# 4ButtonSwitch_Rev2.net
KiCad netlist of a schematic drawn in EAGLE
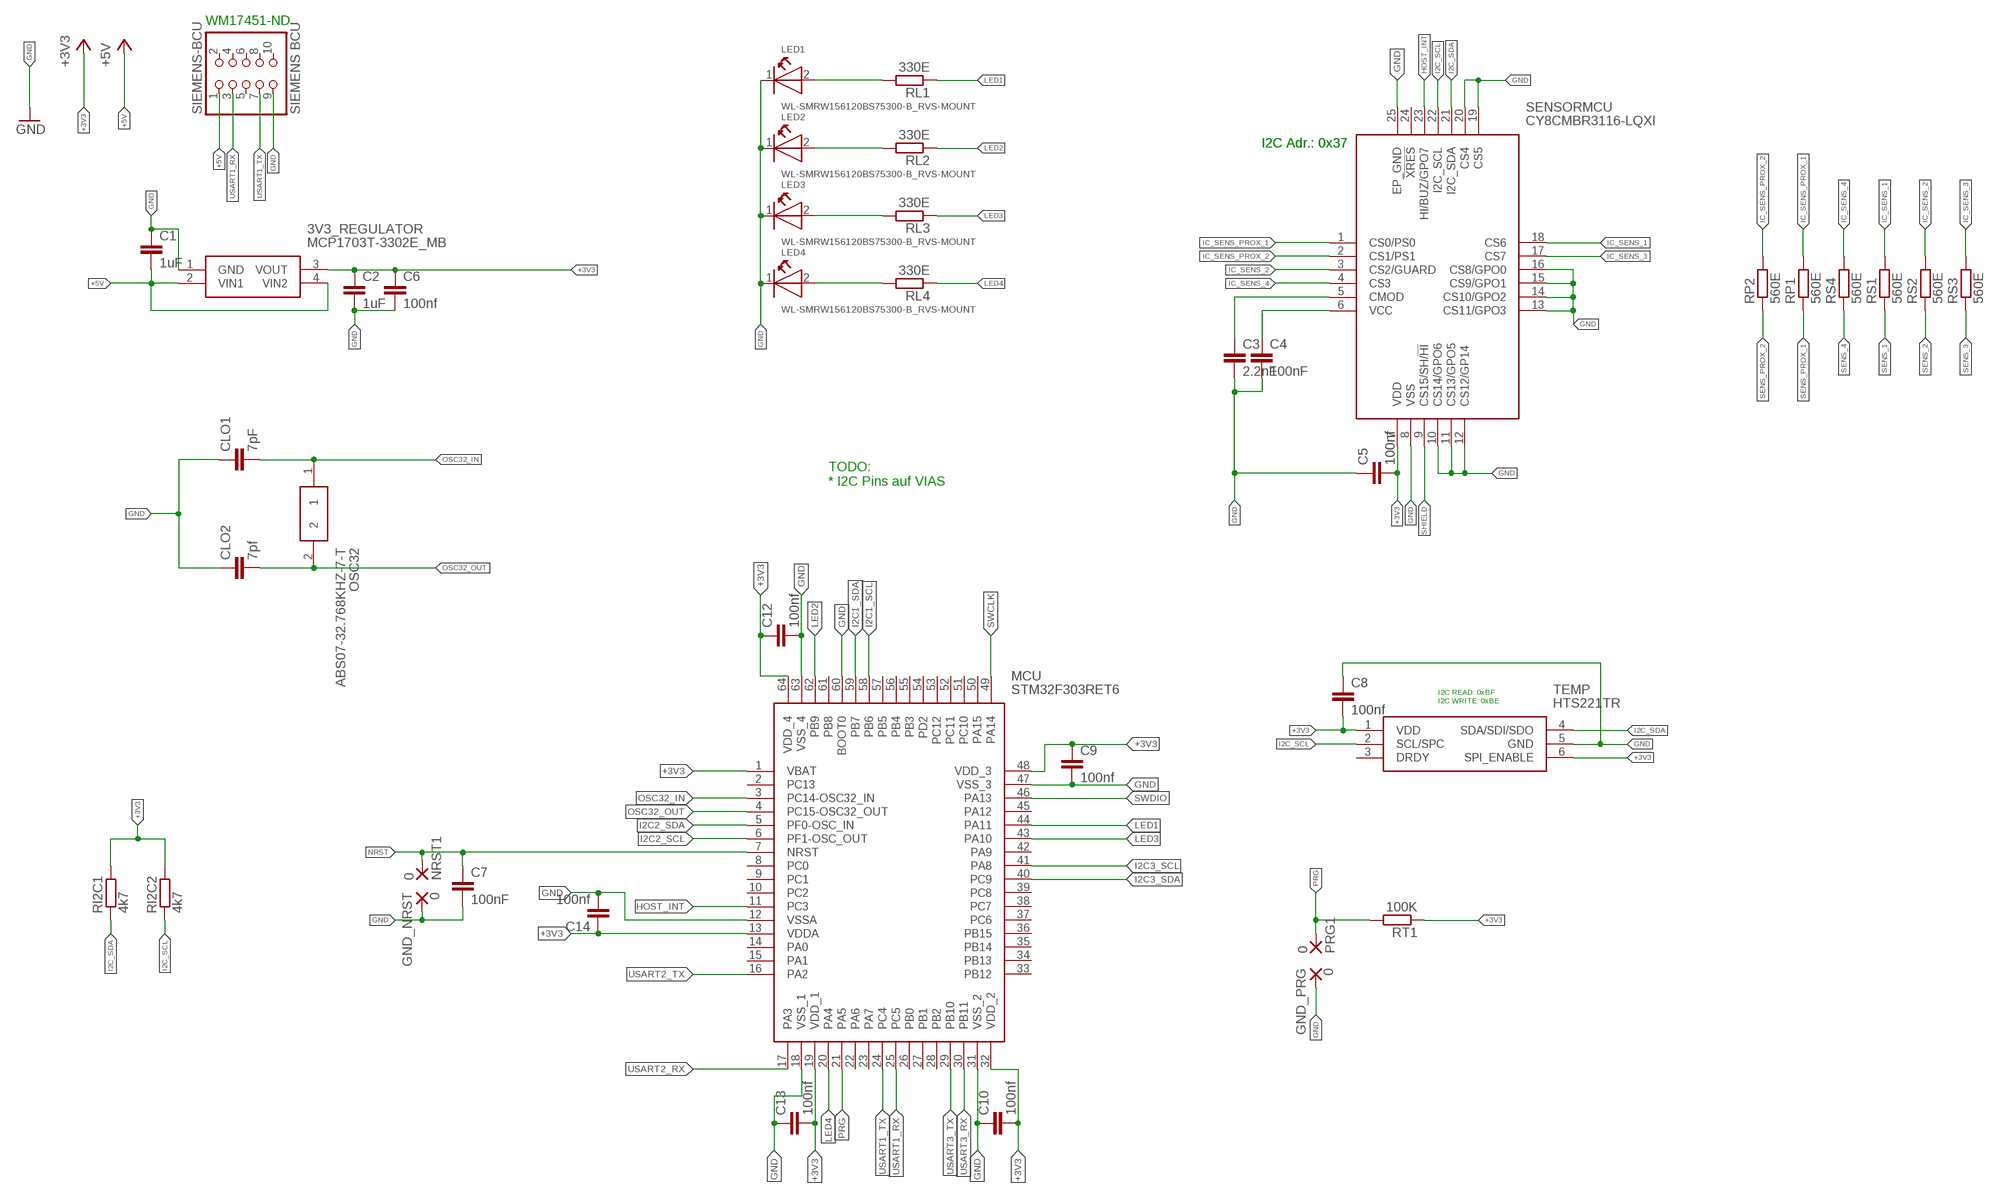
[diagram p0: schematic, sheet 1]

(export (version "E")
  (design (tool "Eeschema 10.0.6"))
  (components
    (comp (ref "3V3_REGULATOR")
      (value "MCP1703T-3302E_MB")
      (footprint "eagle-import:SOT-89(MB)")
      (fields
        (field (name "ARROW_PART_NUMBER") "MCP1703T-3302E/MB")
        (field (name "RS_PART_NUMBER") "9122916")
      )
      (libsource (lib "eagle-import") (part "MCP1703T-3302E_MB"))
    )
    (comp (ref "C1")
      (value "1uF")
      (footprint "eagle-import:C0402")
      (libsource (lib "eagle-import") (part "C-EUC0402"))
    )
    (comp (ref "C2")
      (value "1uF")
      (footprint "eagle-import:C0402")
      (libsource (lib "eagle-import") (part "C-EUC0402"))
    )
    (comp (ref "C3")
      (value "2.2nF")
      (footprint "eagle-import:C0402")
      (libsource (lib "eagle-import") (part "C-EUC0402"))
    )
    (comp (ref "C4")
      (value "100nF")
      (footprint "eagle-import:C0402")
      (libsource (lib "eagle-import") (part "C-EUC0402"))
    )
    (comp (ref "C5")
      (value "100nf")
      (footprint "eagle-import:C0402")
      (libsource (lib "eagle-import") (part "C-EUC0402"))
    )
    (comp (ref "C6")
      (value "100nf")
      (footprint "eagle-import:C0402")
      (libsource (lib "eagle-import") (part "C-EUC0402"))
    )
    (comp (ref "C7")
      (value "100nF")
      (footprint "eagle-import:C0402")
      (libsource (lib "eagle-import") (part "C-EUC0402"))
    )
    (comp (ref "C8")
      (value "100nf")
      (footprint "eagle-import:C0402")
      (libsource (lib "eagle-import") (part "C-EUC0402"))
    )
    (comp (ref "C9")
      (value "100nf")
      (footprint "eagle-import:C0402")
      (libsource (lib "eagle-import") (part "C-EUC0402"))
    )
    (comp (ref "C10")
      (value "100nf")
      (footprint "eagle-import:C0402")
      (libsource (lib "eagle-import") (part "C-EUC0402"))
    )
    (comp (ref "C12")
      (value "100nf")
      (footprint "eagle-import:C0402")
      (libsource (lib "eagle-import") (part "C-EUC0402"))
    )
    (comp (ref "C13")
      (value "100nf")
      (footprint "eagle-import:C0402")
      (libsource (lib "eagle-import") (part "C-EUC0402"))
    )
    (comp (ref "C14")
      (value "100nf")
      (footprint "eagle-import:C0402")
      (libsource (lib "eagle-import") (part "C-EUC0402"))
    )
    (comp (ref "CLO1")
      (value "7pF")
      (footprint "eagle-import:C0402")
      (libsource (lib "eagle-import") (part "C-EUC0402"))
    )
    (comp (ref "CLO2")
      (value "7pf")
      (footprint "eagle-import:C0402")
      (libsource (lib "eagle-import") (part "C-EUC0402"))
    )
    (comp (ref "GND_NRST")
      (value "0")
      (footprint "eagle-import:SMD2,54-5,08")
      (libsource (lib "eagle-import") (part "SMD5"))
    )
    (comp (ref "GND_PRG")
      (value "0")
      (footprint "eagle-import:SMD2,54-5,08")
      (libsource (lib "eagle-import") (part "SMD5"))
    )
    (comp (ref "LED1")
      (value "WL-SMRW156120BS75300-B_RVS-MOUNT")
      (footprint "eagle-import:WL-SMRW-1206-CYLDR-REVERSE-MOUNT")
      (libsource (lib "eagle-import") (part "WL-SMRW156120BS75300-B_RVS-MOUNT"))
    )
    (comp (ref "LED2")
      (value "WL-SMRW156120BS75300-B_RVS-MOUNT")
      (footprint "eagle-import:WL-SMRW-1206-CYLDR-REVERSE-MOUNT")
      (libsource (lib "eagle-import") (part "WL-SMRW156120BS75300-B_RVS-MOUNT"))
    )
    (comp (ref "LED3")
      (value "WL-SMRW156120BS75300-B_RVS-MOUNT")
      (footprint "eagle-import:WL-SMRW-1206-CYLDR-REVERSE-MOUNT")
      (libsource (lib "eagle-import") (part "WL-SMRW156120BS75300-B_RVS-MOUNT"))
    )
    (comp (ref "LED4")
      (value "WL-SMRW156120BS75300-B_RVS-MOUNT")
      (footprint "eagle-import:WL-SMRW-1206-CYLDR-REVERSE-MOUNT")
      (libsource (lib "eagle-import") (part "WL-SMRW156120BS75300-B_RVS-MOUNT"))
    )
    (comp (ref "MCU")
      (value "STM32F303RET6")
      (footprint "eagle-import:QFP50P1200X1200X160-64N")
      (fields (field (name "RS_PART_NUMBER") "1458887"))
      (libsource (lib "eagle-import") (part "STM32F303RET6"))
    )
    (comp (ref "NRST1")
      (value "0")
      (footprint "eagle-import:SMD2,54-5,08")
      (libsource (lib "eagle-import") (part "SMD5"))
    )
    (comp (ref "OSC32")
      (value "ABS07-32.768KHZ-7-T")
      (footprint "eagle-import:ABS-07")
      (fields (field (name "RS_PART_NUMBER") "1712773P"))
      (libsource (lib "eagle-import") (part "ABS07-32.768KHZ-7-T"))
    )
    (comp (ref "PRG1")
      (value "0")
      (footprint "eagle-import:SMD2,54-5,08")
      (libsource (lib "eagle-import") (part "SMD5"))
    )
    (comp (ref "RI2C1")
      (value "4k7")
      (footprint "eagle-import:R0402")
      (libsource (lib "eagle-import") (part "R-EU_R0402"))
    )
    (comp (ref "RI2C2")
      (value "4k7")
      (footprint "eagle-import:R0402")
      (libsource (lib "eagle-import") (part "R-EU_R0402"))
    )
    (comp (ref "RL1")
      (value "330E")
      (footprint "eagle-import:R0402")
      (libsource (lib "eagle-import") (part "R-EU_R0402"))
    )
    (comp (ref "RL2")
      (value "330E")
      (footprint "eagle-import:R0402")
      (libsource (lib "eagle-import") (part "R-EU_R0402"))
    )
    (comp (ref "RL3")
      (value "330E")
      (footprint "eagle-import:R0402")
      (libsource (lib "eagle-import") (part "R-EU_R0402"))
    )
    (comp (ref "RL4")
      (value "330E")
      (footprint "eagle-import:R0402")
      (libsource (lib "eagle-import") (part "R-EU_R0402"))
    )
    (comp (ref "RP1")
      (value "560E")
      (footprint "eagle-import:R0402")
      (libsource (lib "eagle-import") (part "R-EU_R0402"))
    )
    (comp (ref "RP2")
      (value "560E")
      (footprint "eagle-import:R0402")
      (libsource (lib "eagle-import") (part "R-EU_R0402"))
    )
    (comp (ref "RS1")
      (value "560E")
      (footprint "eagle-import:R0402")
      (libsource (lib "eagle-import") (part "R-EU_R0402"))
    )
    (comp (ref "RS2")
      (value "560E")
      (footprint "eagle-import:R0402")
      (libsource (lib "eagle-import") (part "R-EU_R0402"))
    )
    (comp (ref "RS3")
      (value "560E")
      (footprint "eagle-import:R0402")
      (libsource (lib "eagle-import") (part "R-EU_R0402"))
    )
    (comp (ref "RS4")
      (value "560E")
      (footprint "eagle-import:R0402")
      (libsource (lib "eagle-import") (part "R-EU_R0402"))
    )
    (comp (ref "RT1")
      (value "100K")
      (footprint "eagle-import:R0402")
      (libsource (lib "eagle-import") (part "R-EU_R0402"))
    )
    (comp (ref "SENSORMCU")
      (value "CY8CMBR3116-LQXI")
      (footprint "eagle-import:QFN50P400X400X60-25N")
      (fields (field (name "RS_PART_NUMBER") "1242976P"))
      (libsource (lib "eagle-import") (part "CY8CMBR3116-LQXI"))
    )
    (comp (ref "SIEMENS-BCU")
      (value "SIEMENS BCU")
      (footprint "eagle-import:2X05SMD")
      (libsource (lib "eagle-import") (part "PINHD-2X5_2.54-SMD"))
    )
    (comp (ref "TEMP")
      (value "HTS221TR")
      (footprint "eagle-import:HLGA-6L")
      (fields (field (name "RS_PART_NUMBER") "1660935"))
      (libsource (lib "eagle-import") (part "HTS221TR"))
    )
  )
  (nets
    (net (code "1") (name "+3V3") (class "Default")
      (node (ref "3V3_REGULATOR") (pin "3") (pinfunction "VOUT_3") (pintype "bidirectional"))
      (node (ref "C10") (pin "2") (pinfunction "2_2") (pintype "passive"))
      (node (ref "C12") (pin "1") (pinfunction "1_1") (pintype "passive"))
      (node (ref "C13") (pin "2") (pinfunction "2_2") (pintype "passive"))
      (node (ref "C14") (pin "1") (pinfunction "1_1") (pintype "passive"))
      (node (ref "C2") (pin "1") (pinfunction "1_1") (pintype "passive"))
      (node (ref "C5") (pin "2") (pinfunction "2_2") (pintype "passive"))
      (node (ref "C6") (pin "1") (pinfunction "1_1") (pintype "passive"))
      (node (ref "C8") (pin "2") (pinfunction "2_2") (pintype "passive"))
      (node (ref "C9") (pin "1") (pinfunction "1_1") (pintype "passive"))
      (node (ref "MCU") (pin "1") (pinfunction "VBAT_1") (pintype "power_in"))
      (node (ref "MCU") (pin "13") (pinfunction "VDDA_13") (pintype "power_in"))
      (node (ref "MCU") (pin "19") (pinfunction "VDD_1_19") (pintype "power_in"))
      (node (ref "MCU") (pin "32") (pinfunction "VDD_2_32") (pintype "power_in"))
      (node (ref "MCU") (pin "48") (pinfunction "VDD_3_48") (pintype "power_in"))
      (node (ref "MCU") (pin "64") (pinfunction "VDD_4_64") (pintype "power_in"))
      (node (ref "RI2C1") (pin "2") (pinfunction "2_2") (pintype "passive"))
      (node (ref "RI2C2") (pin "2") (pinfunction "2_2") (pintype "passive"))
      (node (ref "RT1") (pin "1") (pinfunction "1_1") (pintype "passive"))
      (node (ref "SENSORMCU") (pin "7") (pinfunction "VDD_7") (pintype "power_in"))
      (node (ref "TEMP") (pin "1") (pinfunction "VDD_1") (pintype "bidirectional"))
      (node (ref "TEMP") (pin "6") (pinfunction "SPI_ENABLE_6") (pintype "bidirectional"))
    )
    (net (code "2") (name "+5V") (class "Default")
      (node (ref "3V3_REGULATOR") (pin "2") (pinfunction "VIN1_2") (pintype "bidirectional"))
      (node (ref "3V3_REGULATOR") (pin "4") (pinfunction "VIN2_4") (pintype "bidirectional"))
      (node (ref "C1") (pin "2") (pinfunction "2_2") (pintype "passive"))
      (node (ref "SIEMENS-BCU") (pin "1") (pinfunction "1_1") (pintype "passive"))
    )
    (net (code "3") (name "GND") (class "Default")
      (node (ref "3V3_REGULATOR") (pin "1") (pinfunction "GND_1") (pintype "bidirectional"))
      (node (ref "C1") (pin "1") (pinfunction "1_1") (pintype "passive"))
      (node (ref "C10") (pin "1") (pinfunction "1_1") (pintype "passive"))
      (node (ref "C12") (pin "2") (pinfunction "2_2") (pintype "passive"))
      (node (ref "C13") (pin "1") (pinfunction "1_1") (pintype "passive"))
      (node (ref "C14") (pin "2") (pinfunction "2_2") (pintype "passive"))
      (node (ref "C2") (pin "2") (pinfunction "2_2") (pintype "passive"))
      (node (ref "C3") (pin "2") (pinfunction "2_2") (pintype "passive"))
      (node (ref "C4") (pin "2") (pinfunction "2_2") (pintype "passive"))
      (node (ref "C5") (pin "1") (pinfunction "1_1") (pintype "passive"))
      (node (ref "C6") (pin "2") (pinfunction "2_2") (pintype "passive"))
      (node (ref "C7") (pin "2") (pinfunction "2_2") (pintype "passive"))
      (node (ref "C8") (pin "1") (pinfunction "1_1") (pintype "passive"))
      (node (ref "C9") (pin "2") (pinfunction "2_2") (pintype "passive"))
      (node (ref "CLO1") (pin "1") (pinfunction "1_1") (pintype "passive"))
      (node (ref "CLO2") (pin "1") (pinfunction "1_1") (pintype "passive"))
      (node (ref "GND_NRST") (pin "1") (pinfunction "P_1") (pintype "passive"))
      (node (ref "GND_PRG") (pin "1") (pinfunction "P_1") (pintype "passive"))
      (node (ref "LED1") (pin "1") (pinfunction "K_1") (pintype "bidirectional"))
      (node (ref "LED2") (pin "1") (pinfunction "K_1") (pintype "bidirectional"))
      (node (ref "LED3") (pin "1") (pinfunction "K_1") (pintype "bidirectional"))
      (node (ref "LED4") (pin "1") (pinfunction "K_1") (pintype "bidirectional"))
      (node (ref "MCU") (pin "12") (pinfunction "VSSA_12") (pintype "power_in"))
      (node (ref "MCU") (pin "18") (pinfunction "VSS_1_18") (pintype "power_in"))
      (node (ref "MCU") (pin "31") (pinfunction "VSS_2_31") (pintype "power_in"))
      (node (ref "MCU") (pin "47") (pinfunction "VSS_3_47") (pintype "power_in"))
      (node (ref "MCU") (pin "60") (pinfunction "BOOT0_60") (pintype "bidirectional"))
      (node (ref "MCU") (pin "63") (pinfunction "VSS_4_63") (pintype "power_in"))
      (node (ref "SENSORMCU") (pin "10") (pinfunction "CS14/GPO6_10") (pintype "input"))
      (node (ref "SENSORMCU") (pin "11") (pinfunction "CS13/GPO5_11") (pintype "input"))
      (node (ref "SENSORMCU") (pin "12") (pinfunction "CS12/GP14_12") (pintype "input"))
      (node (ref "SENSORMCU") (pin "13") (pinfunction "CS11/GPO3_13") (pintype "input"))
      (node (ref "SENSORMCU") (pin "14") (pinfunction "CS10/GPO2_14") (pintype "input"))
      (node (ref "SENSORMCU") (pin "15") (pinfunction "CS9/GPO1_15") (pintype "input"))
      (node (ref "SENSORMCU") (pin "16") (pinfunction "CS8/GPO0_16") (pintype "input"))
      (node (ref "SENSORMCU") (pin "19") (pinfunction "CS5_19") (pintype "input"))
      (node (ref "SENSORMCU") (pin "20") (pinfunction "CS4_20") (pintype "input"))
      (node (ref "SENSORMCU") (pin "25") (pinfunction "EP_GND_25") (pintype "power_in"))
      (node (ref "SENSORMCU") (pin "8") (pinfunction "VSS_8") (pintype "power_in"))
      (node (ref "SIEMENS-BCU") (pin "9") (pinfunction "9_9") (pintype "passive"))
      (node (ref "TEMP") (pin "5") (pinfunction "GND_5") (pintype "bidirectional"))
    )
    (net (code "4") (name "HOST_INT") (class "Default")
      (node (ref "MCU") (pin "11") (pinfunction "PC3_11") (pintype "bidirectional"))
      (node (ref "SENSORMCU") (pin "23") (pinfunction "HI/BUZ/GPO7_23") (pintype "bidirectional"))
    )
    (net (code "5") (name "I2C1_SCL") (class "Default")
      (node (ref "MCU") (pin "58") (pinfunction "PB6_58") (pintype "bidirectional"))
    )
    (net (code "6") (name "I2C1_SDA") (class "Default")
      (node (ref "MCU") (pin "59") (pinfunction "PB7_59") (pintype "bidirectional"))
    )
    (net (code "7") (name "I2C2_SCL") (class "Default")
      (node (ref "MCU") (pin "6") (pinfunction "PF1-OSC_OUT_6") (pintype "bidirectional"))
    )
    (net (code "8") (name "I2C2_SDA") (class "Default")
      (node (ref "MCU") (pin "5") (pinfunction "PF0-OSC_IN_5") (pintype "bidirectional"))
    )
    (net (code "9") (name "I2C3_SCL") (class "Default")
      (node (ref "MCU") (pin "41") (pinfunction "PA8_41") (pintype "bidirectional"))
    )
    (net (code "10") (name "I2C3_SDA") (class "Default")
      (node (ref "MCU") (pin "40") (pinfunction "PC9_40") (pintype "bidirectional"))
    )
    (net (code "11") (name "I2C_SCL") (class "Default")
      (node (ref "RI2C2") (pin "1") (pinfunction "1_1") (pintype "passive"))
      (node (ref "SENSORMCU") (pin "22") (pinfunction "I2C_SCL_22") (pintype "bidirectional"))
      (node (ref "TEMP") (pin "2") (pinfunction "SCL/SPC_2") (pintype "bidirectional"))
    )
    (net (code "12") (name "I2C_SDA") (class "Default")
      (node (ref "RI2C1") (pin "1") (pinfunction "1_1") (pintype "passive"))
      (node (ref "SENSORMCU") (pin "21") (pinfunction "I2C_SDA_21") (pintype "bidirectional"))
      (node (ref "TEMP") (pin "4") (pinfunction "SDA/SDI/SDO_4") (pintype "bidirectional"))
    )
    (net (code "13") (name "IC_SENS_1") (class "Default")
      (node (ref "RS1") (pin "2") (pinfunction "2_2") (pintype "passive"))
      (node (ref "SENSORMCU") (pin "18") (pinfunction "CS6_18") (pintype "input"))
    )
    (net (code "14") (name "IC_SENS_2") (class "Default")
      (node (ref "RS2") (pin "2") (pinfunction "2_2") (pintype "passive"))
      (node (ref "SENSORMCU") (pin "3") (pinfunction "CS2/GUARD_3") (pintype "input"))
    )
    (net (code "15") (name "IC_SENS_3") (class "Default")
      (node (ref "RS3") (pin "2") (pinfunction "2_2") (pintype "passive"))
      (node (ref "SENSORMCU") (pin "17") (pinfunction "CS7_17") (pintype "input"))
    )
    (net (code "16") (name "IC_SENS_4") (class "Default")
      (node (ref "RS4") (pin "2") (pinfunction "2_2") (pintype "passive"))
      (node (ref "SENSORMCU") (pin "4") (pinfunction "CS3_4") (pintype "input"))
    )
    (net (code "17") (name "IC_SENS_PROX_1") (class "Default")
      (node (ref "RP1") (pin "2") (pinfunction "2_2") (pintype "passive"))
      (node (ref "SENSORMCU") (pin "1") (pinfunction "CS0/PS0_1") (pintype "input"))
    )
    (net (code "18") (name "IC_SENS_PROX_2") (class "Default")
      (node (ref "RP2") (pin "2") (pinfunction "2_2") (pintype "passive"))
      (node (ref "SENSORMCU") (pin "2") (pinfunction "CS1/PS1_2") (pintype "input"))
    )
    (net (code "19") (name "LED1") (class "Default")
      (node (ref "MCU") (pin "44") (pinfunction "PA11_44") (pintype "bidirectional"))
      (node (ref "RL1") (pin "1") (pinfunction "1_1") (pintype "passive"))
    )
    (net (code "20") (name "LED2") (class "Default")
      (node (ref "MCU") (pin "62") (pinfunction "PB9_62") (pintype "bidirectional"))
      (node (ref "RL2") (pin "1") (pinfunction "1_1") (pintype "passive"))
    )
    (net (code "21") (name "LED3") (class "Default")
      (node (ref "MCU") (pin "43") (pinfunction "PA10_43") (pintype "bidirectional"))
      (node (ref "RL3") (pin "1") (pinfunction "1_1") (pintype "passive"))
    )
    (net (code "22") (name "LED4") (class "Default")
      (node (ref "MCU") (pin "20") (pinfunction "PA4_20") (pintype "bidirectional"))
      (node (ref "RL4") (pin "1") (pinfunction "1_1") (pintype "passive"))
    )
    (net (code "23") (name "NRST") (class "Default")
      (node (ref "C7") (pin "1") (pinfunction "1_1") (pintype "passive"))
      (node (ref "MCU") (pin "7") (pinfunction "NRST_7") (pintype "bidirectional"))
      (node (ref "NRST1") (pin "1") (pinfunction "P_1") (pintype "passive"))
    )
    (net (code "24") (name "Net-(LED1-A)") (class "Default")
      (node (ref "LED1") (pin "2") (pinfunction "A_2") (pintype "bidirectional"))
      (node (ref "RL1") (pin "2") (pinfunction "2_2") (pintype "passive"))
    )
    (net (code "25") (name "Net-(LED2-A)") (class "Default")
      (node (ref "LED2") (pin "2") (pinfunction "A_2") (pintype "bidirectional"))
      (node (ref "RL2") (pin "2") (pinfunction "2_2") (pintype "passive"))
    )
    (net (code "26") (name "Net-(LED3-A)") (class "Default")
      (node (ref "LED3") (pin "2") (pinfunction "A_2") (pintype "bidirectional"))
      (node (ref "RL3") (pin "2") (pinfunction "2_2") (pintype "passive"))
    )
    (net (code "27") (name "Net-(LED4-A)") (class "Default")
      (node (ref "LED4") (pin "2") (pinfunction "A_2") (pintype "bidirectional"))
      (node (ref "RL4") (pin "2") (pinfunction "2_2") (pintype "passive"))
    )
    (net (code "28") (name "Net-(SENSORMCU-CMOD)") (class "Default")
      (node (ref "C3") (pin "1") (pinfunction "1_1") (pintype "passive"))
      (node (ref "SENSORMCU") (pin "5") (pinfunction "CMOD_5") (pintype "bidirectional"))
    )
    (net (code "29") (name "Net-(SENSORMCU-VCC)") (class "Default")
      (node (ref "C4") (pin "1") (pinfunction "1_1") (pintype "passive"))
      (node (ref "SENSORMCU") (pin "6") (pinfunction "VCC_6") (pintype "power_in"))
    )
    (net (code "30") (name "OSC32_IN") (class "Default")
      (node (ref "CLO1") (pin "2") (pinfunction "2_2") (pintype "passive"))
      (node (ref "MCU") (pin "3") (pinfunction "PC14-OSC32_IN_3") (pintype "bidirectional"))
      (node (ref "OSC32") (pin "1") (pinfunction "1_1") (pintype "bidirectional"))
    )
    (net (code "31") (name "OSC32_OUT") (class "Default")
      (node (ref "CLO2") (pin "2") (pinfunction "2_2") (pintype "passive"))
      (node (ref "MCU") (pin "4") (pinfunction "PC15-OSC32_OUT_4") (pintype "bidirectional"))
      (node (ref "OSC32") (pin "2") (pinfunction "2_2") (pintype "bidirectional"))
    )
    (net (code "32") (name "PRG") (class "Default")
      (node (ref "MCU") (pin "21") (pinfunction "PA5_21") (pintype "bidirectional"))
      (node (ref "PRG1") (pin "1") (pinfunction "P_1") (pintype "passive"))
      (node (ref "RT1") (pin "2") (pinfunction "2_2") (pintype "passive"))
    )
    (net (code "33") (name "SENS_1") (class "Default")
      (node (ref "RS1") (pin "1") (pinfunction "1_1") (pintype "passive"))
    )
    (net (code "34") (name "SENS_2") (class "Default")
      (node (ref "RS2") (pin "1") (pinfunction "1_1") (pintype "passive"))
    )
    (net (code "35") (name "SENS_3") (class "Default")
      (node (ref "RS3") (pin "1") (pinfunction "1_1") (pintype "passive"))
    )
    (net (code "36") (name "SENS_4") (class "Default")
      (node (ref "RS4") (pin "1") (pinfunction "1_1") (pintype "passive"))
    )
    (net (code "37") (name "SENS_PROX_1") (class "Default")
      (node (ref "RP1") (pin "1") (pinfunction "1_1") (pintype "passive"))
    )
    (net (code "38") (name "SENS_PROX_2") (class "Default")
      (node (ref "RP2") (pin "1") (pinfunction "1_1") (pintype "passive"))
    )
    (net (code "39") (name "SHIELD") (class "Default")
      (node (ref "SENSORMCU") (pin "9") (pinfunction "CS15/SH/~{HI}_9") (pintype "input"))
    )
    (net (code "40") (name "SWCLK") (class "Default")
      (node (ref "MCU") (pin "49") (pinfunction "PA14_49") (pintype "bidirectional"))
    )
    (net (code "41") (name "SWDIO") (class "Default")
      (node (ref "MCU") (pin "46") (pinfunction "PA13_46") (pintype "bidirectional"))
    )
    (net (code "42") (name "USART1_RX") (class "Default")
      (node (ref "MCU") (pin "25") (pinfunction "PC5_25") (pintype "bidirectional"))
      (node (ref "SIEMENS-BCU") (pin "3") (pinfunction "3_3") (pintype "passive"))
    )
    (net (code "43") (name "USART1_TX") (class "Default")
      (node (ref "MCU") (pin "24") (pinfunction "PC4_24") (pintype "bidirectional"))
      (node (ref "SIEMENS-BCU") (pin "7") (pinfunction "7_7") (pintype "passive"))
    )
    (net (code "44") (name "USART2_RX") (class "Default")
      (node (ref "MCU") (pin "17") (pinfunction "PA3_17") (pintype "bidirectional"))
    )
    (net (code "45") (name "USART2_TX") (class "Default")
      (node (ref "MCU") (pin "16") (pinfunction "PA2_16") (pintype "bidirectional"))
    )
    (net (code "46") (name "USART3_RX") (class "Default")
      (node (ref "MCU") (pin "30") (pinfunction "PB11_30") (pintype "bidirectional"))
    )
    (net (code "47") (name "USART3_TX") (class "Default")
      (node (ref "MCU") (pin "29") (pinfunction "PB10_29") (pintype "bidirectional"))
    )
    (net (code "48") (name "unconnected-(MCU-PA0-Pad14)") (class "Default")
      (node (ref "MCU") (pin "14") (pinfunction "PA0_14") (pintype "bidirectional"))
    )
    (net (code "49") (name "unconnected-(MCU-PA1-Pad15)") (class "Default")
      (node (ref "MCU") (pin "15") (pinfunction "PA1_15") (pintype "bidirectional"))
    )
    (net (code "50") (name "unconnected-(MCU-PA6-Pad22)") (class "Default")
      (node (ref "MCU") (pin "22") (pinfunction "PA6_22") (pintype "bidirectional"))
    )
    (net (code "51") (name "unconnected-(MCU-PA7-Pad23)") (class "Default")
      (node (ref "MCU") (pin "23") (pinfunction "PA7_23") (pintype "bidirectional"))
    )
    (net (code "52") (name "unconnected-(MCU-PA9-Pad42)") (class "Default")
      (node (ref "MCU") (pin "42") (pinfunction "PA9_42") (pintype "bidirectional"))
    )
    (net (code "53") (name "unconnected-(MCU-PA12-Pad45)") (class "Default")
      (node (ref "MCU") (pin "45") (pinfunction "PA12_45") (pintype "bidirectional"))
    )
    (net (code "54") (name "unconnected-(MCU-PA15-Pad50)") (class "Default")
      (node (ref "MCU") (pin "50") (pinfunction "PA15_50") (pintype "bidirectional"))
    )
    (net (code "55") (name "unconnected-(MCU-PB0-Pad26)") (class "Default")
      (node (ref "MCU") (pin "26") (pinfunction "PB0_26") (pintype "bidirectional"))
    )
    (net (code "56") (name "unconnected-(MCU-PB1-Pad27)") (class "Default")
      (node (ref "MCU") (pin "27") (pinfunction "PB1_27") (pintype "bidirectional"))
    )
    (net (code "57") (name "unconnected-(MCU-PB2-Pad28)") (class "Default")
      (node (ref "MCU") (pin "28") (pinfunction "PB2_28") (pintype "bidirectional"))
    )
    (net (code "58") (name "unconnected-(MCU-PB3-Pad55)") (class "Default")
      (node (ref "MCU") (pin "55") (pinfunction "PB3_55") (pintype "bidirectional"))
    )
    (net (code "59") (name "unconnected-(MCU-PB4-Pad56)") (class "Default")
      (node (ref "MCU") (pin "56") (pinfunction "PB4_56") (pintype "bidirectional"))
    )
    (net (code "60") (name "unconnected-(MCU-PB5-Pad57)") (class "Default")
      (node (ref "MCU") (pin "57") (pinfunction "PB5_57") (pintype "bidirectional"))
    )
    (net (code "61") (name "unconnected-(MCU-PB8-Pad61)") (class "Default")
      (node (ref "MCU") (pin "61") (pinfunction "PB8_61") (pintype "bidirectional"))
    )
    (net (code "62") (name "unconnected-(MCU-PB12-Pad33)") (class "Default")
      (node (ref "MCU") (pin "33") (pinfunction "PB12_33") (pintype "bidirectional"))
    )
    (net (code "63") (name "unconnected-(MCU-PB13-Pad34)") (class "Default")
      (node (ref "MCU") (pin "34") (pinfunction "PB13_34") (pintype "bidirectional"))
    )
    (net (code "64") (name "unconnected-(MCU-PB14-Pad35)") (class "Default")
      (node (ref "MCU") (pin "35") (pinfunction "PB14_35") (pintype "bidirectional"))
    )
    (net (code "65") (name "unconnected-(MCU-PB15-Pad36)") (class "Default")
      (node (ref "MCU") (pin "36") (pinfunction "PB15_36") (pintype "bidirectional"))
    )
    (net (code "66") (name "unconnected-(MCU-PC0-Pad8)") (class "Default")
      (node (ref "MCU") (pin "8") (pinfunction "PC0_8") (pintype "bidirectional"))
    )
    (net (code "67") (name "unconnected-(MCU-PC1-Pad9)") (class "Default")
      (node (ref "MCU") (pin "9") (pinfunction "PC1_9") (pintype "bidirectional"))
    )
    (net (code "68") (name "unconnected-(MCU-PC2-Pad10)") (class "Default")
      (node (ref "MCU") (pin "10") (pinfunction "PC2_10") (pintype "bidirectional"))
    )
    (net (code "69") (name "unconnected-(MCU-PC6-Pad37)") (class "Default")
      (node (ref "MCU") (pin "37") (pinfunction "PC6_37") (pintype "bidirectional"))
    )
    (net (code "70") (name "unconnected-(MCU-PC7-Pad38)") (class "Default")
      (node (ref "MCU") (pin "38") (pinfunction "PC7_38") (pintype "bidirectional"))
    )
    (net (code "71") (name "unconnected-(MCU-PC8-Pad39)") (class "Default")
      (node (ref "MCU") (pin "39") (pinfunction "PC8_39") (pintype "bidirectional"))
    )
    (net (code "72") (name "unconnected-(MCU-PC10-Pad51)") (class "Default")
      (node (ref "MCU") (pin "51") (pinfunction "PC10_51") (pintype "bidirectional"))
    )
    (net (code "73") (name "unconnected-(MCU-PC11-Pad52)") (class "Default")
      (node (ref "MCU") (pin "52") (pinfunction "PC11_52") (pintype "bidirectional"))
    )
    (net (code "74") (name "unconnected-(MCU-PC12-Pad53)") (class "Default")
      (node (ref "MCU") (pin "53") (pinfunction "PC12_53") (pintype "bidirectional"))
    )
    (net (code "75") (name "unconnected-(MCU-PC13-Pad2)") (class "Default")
      (node (ref "MCU") (pin "2") (pinfunction "PC13_2") (pintype "bidirectional"))
    )
    (net (code "76") (name "unconnected-(MCU-PD2-Pad54)") (class "Default")
      (node (ref "MCU") (pin "54") (pinfunction "PD2_54") (pintype "bidirectional"))
    )
    (net (code "77") (name "unconnected-(SENSORMCU-~{XRES}-Pad24)") (class "Default")
      (node (ref "SENSORMCU") (pin "24") (pinfunction "~{XRES}_24") (pintype "bidirectional"))
    )
    (net (code "78") (name "unconnected-(SIEMENS-BCU-Pad2)") (class "Default")
      (node (ref "SIEMENS-BCU") (pin "2") (pinfunction "2_2") (pintype "passive"))
    )
    (net (code "79") (name "unconnected-(SIEMENS-BCU-Pad4)") (class "Default")
      (node (ref "SIEMENS-BCU") (pin "4") (pinfunction "4_4") (pintype "passive"))
    )
    (net (code "80") (name "unconnected-(SIEMENS-BCU-Pad5)") (class "Default")
      (node (ref "SIEMENS-BCU") (pin "5") (pinfunction "5_5") (pintype "passive"))
    )
    (net (code "81") (name "unconnected-(SIEMENS-BCU-Pad6)") (class "Default")
      (node (ref "SIEMENS-BCU") (pin "6") (pinfunction "6_6") (pintype "passive"))
    )
    (net (code "82") (name "unconnected-(SIEMENS-BCU-Pad8)") (class "Default")
      (node (ref "SIEMENS-BCU") (pin "8") (pinfunction "8_8") (pintype "passive"))
    )
    (net (code "83") (name "unconnected-(SIEMENS-BCU-Pad10)") (class "Default")
      (node (ref "SIEMENS-BCU") (pin "10") (pinfunction "10_10") (pintype "passive"))
    )
    (net (code "84") (name "unconnected-(TEMP-DRDY-Pad3)") (class "Default")
      (node (ref "TEMP") (pin "3") (pinfunction "DRDY_3") (pintype "bidirectional"))
    )
  )
)
